# Connectors_General.net
KiCad netlist of a schematic drawn in Altium Designer
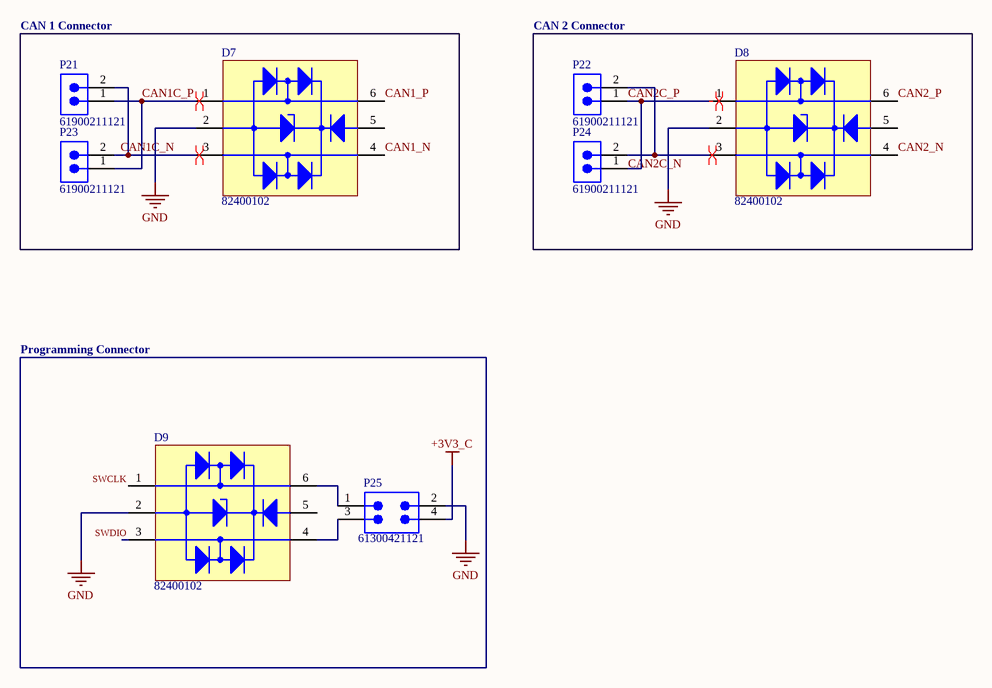
[diagram p0: Connectors_General.SchDoc]

(export (version "E")
  (design (tool "Eeschema 10.0.6"))
  (components
    (comp (ref "D7")
      (value "82400102")
      (footprint "WE-TVS_SOT23-6L")
      (description "WE-TVS TVS Diode – High Speed Series, SOT23-6L, 2+1 Channel, 5V, 2pF")
      (fields (field (name "MANUFACTURER") "Wurth Elektronik"))
      (libsource (lib "LEEM UPM") (part "82400152"))
    )
    (comp (ref "D8")
      (value "82400102")
      (footprint "WE-TVS_SOT23-6L")
      (description "WE-TVS TVS Diode – High Speed Series, SOT23-6L, 2+1 Channel, 5V, 2pF")
      (fields (field (name "MANUFACTURER") "Wurth Elektronik"))
      (libsource (lib "LEEM UPM") (part "82400152"))
    )
    (comp (ref "D9")
      (value "82400102")
      (footprint "WE-TVS_SOT23-6L")
      (description "WE-TVS TVS Diode – High Speed Series, SOT23-6L, 2+1 Channel, 5V, 2pF")
      (fields (field (name "MANUFACTURER") "Wurth Elektronik"))
      (libsource (lib "LEEM UPM") (part "82400152"))
    )
    (comp (ref "P21")
      (value "61900211121")
      (footprint "61900211121")
      (description "WR-WTB THT Male Vertical Locking Header, pitch 2.54mm, 2pins")
      (fields (field (name "MANUFACTURER") "Wurth Elektronik"))
      (libsource (lib "LEEM UPM") (part "679302124022"))
    )
    (comp (ref "P22")
      (value "61900211121")
      (footprint "61900211121")
      (description "WR-WTB THT Male Vertical Locking Header, pitch 2.54mm, 2pins")
      (fields (field (name "MANUFACTURER") "Wurth Elektronik"))
      (libsource (lib "LEEM UPM") (part "679302124022"))
    )
    (comp (ref "P23")
      (value "61900211121")
      (footprint "61900211121")
      (description "WR-WTB THT Male Vertical Locking Header, pitch 2.54mm, 2pins")
      (fields (field (name "MANUFACTURER") "Wurth Elektronik"))
      (libsource (lib "LEEM UPM") (part "679302124022"))
    )
    (comp (ref "P24")
      (value "61900211121")
      (footprint "61900211121")
      (description "WR-WTB THT Male Vertical Locking Header, pitch 2.54mm, 2pins")
      (fields (field (name "MANUFACTURER") "Wurth Elektronik"))
      (libsource (lib "LEEM UPM") (part "679302124022"))
    )
    (comp (ref "P25")
      (value "61300421121")
      (footprint "61300421121")
      (libsource (lib "LEEM UPM") (part "Header_Male_2R_04P"))
    )
  )
  (nets
    (net (code "1") (name "+3V3_C") (class "Default")
      (node (ref "P25") (pin "4") (pinfunction "4_4") (pintype "passive"))
    )
    (net (code "2") (name "/CAN1C_N") (class "Default")
      (node (ref "D7") (pin "3") (pinfunction "I/O_2_3") (pintype "passive"))
      (node (ref "P21") (pin "2") (pinfunction "2_2") (pintype "passive"))
      (node (ref "P23") (pin "2") (pinfunction "2_2") (pintype "passive"))
    )
    (net (code "3") (name "/CAN1C_P") (class "Default")
      (node (ref "D7") (pin "1") (pinfunction "I/O_1_1") (pintype "passive"))
      (node (ref "P21") (pin "1") (pinfunction "1_1") (pintype "passive"))
      (node (ref "P23") (pin "1") (pinfunction "1_1") (pintype "passive"))
    )
    (net (code "4") (name "/CAN1_N") (class "Default")
      (node (ref "D7") (pin "4") (pinfunction "I/O_2_4") (pintype "passive"))
    )
    (net (code "5") (name "/CAN1_P") (class "Default")
      (node (ref "D7") (pin "6") (pinfunction "I/O_1_6") (pintype "passive"))
    )
    (net (code "6") (name "/CAN2C_N") (class "Default")
      (node (ref "D8") (pin "3") (pinfunction "I/O_2_3") (pintype "passive"))
      (node (ref "P22") (pin "2") (pinfunction "2_2") (pintype "passive"))
      (node (ref "P24") (pin "2") (pinfunction "2_2") (pintype "passive"))
    )
    (net (code "7") (name "/CAN2C_P") (class "Default")
      (node (ref "D8") (pin "1") (pinfunction "I/O_1_1") (pintype "passive"))
      (node (ref "P22") (pin "1") (pinfunction "1_1") (pintype "passive"))
      (node (ref "P24") (pin "1") (pinfunction "1_1") (pintype "passive"))
    )
    (net (code "8") (name "/CAN2_N") (class "Default")
      (node (ref "D8") (pin "4") (pinfunction "I/O_2_4") (pintype "passive"))
    )
    (net (code "9") (name "/CAN2_P") (class "Default")
      (node (ref "D8") (pin "6") (pinfunction "I/O_1_6") (pintype "passive"))
    )
    (net (code "10") (name "/SWCLK") (class "Default")
      (node (ref "D9") (pin "1") (pinfunction "I/O_1_1") (pintype "passive"))
    )
    (net (code "11") (name "/SWDIO") (class "Default")
      (node (ref "D9") (pin "3") (pinfunction "I/O_2_3") (pintype "passive"))
    )
    (net (code "12") (name "GND") (class "Default")
      (node (ref "D7") (pin "2") (pinfunction "GND_2") (pintype "passive"))
      (node (ref "D8") (pin "2") (pinfunction "GND_2") (pintype "passive"))
      (node (ref "D9") (pin "2") (pinfunction "GND_2") (pintype "passive"))
      (node (ref "P25") (pin "2") (pinfunction "2_2") (pintype "passive"))
    )
    (net (code "13") (name "Net-(D9-I{slash}O_1-Pad6)") (class "Default")
      (node (ref "D9") (pin "6") (pinfunction "I/O_1_6") (pintype "passive"))
      (node (ref "P25") (pin "1") (pinfunction "1_1") (pintype "passive"))
    )
    (net (code "14") (name "Net-(D9-I{slash}O_2-Pad4)") (class "Default")
      (node (ref "D9") (pin "4") (pinfunction "I/O_2_4") (pintype "passive"))
      (node (ref "P25") (pin "3") (pinfunction "3_3") (pintype "passive"))
    )
    (net (code "15") (name "unconnected-(D7-VDD-Pad5)") (class "Default")
      (node (ref "D7") (pin "5") (pinfunction "VDD_5") (pintype "passive"))
    )
    (net (code "16") (name "unconnected-(D8-VDD-Pad5)") (class "Default")
      (node (ref "D8") (pin "5") (pinfunction "VDD_5") (pintype "passive"))
    )
    (net (code "17") (name "unconnected-(D9-VDD-Pad5)") (class "Default")
      (node (ref "D9") (pin "5") (pinfunction "VDD_5") (pintype "passive"))
    )
  )
)
